# navilock-gps-to-bluetooth-converter-v1_2.net
KiCad netlist of a schematic drawn in EAGLE
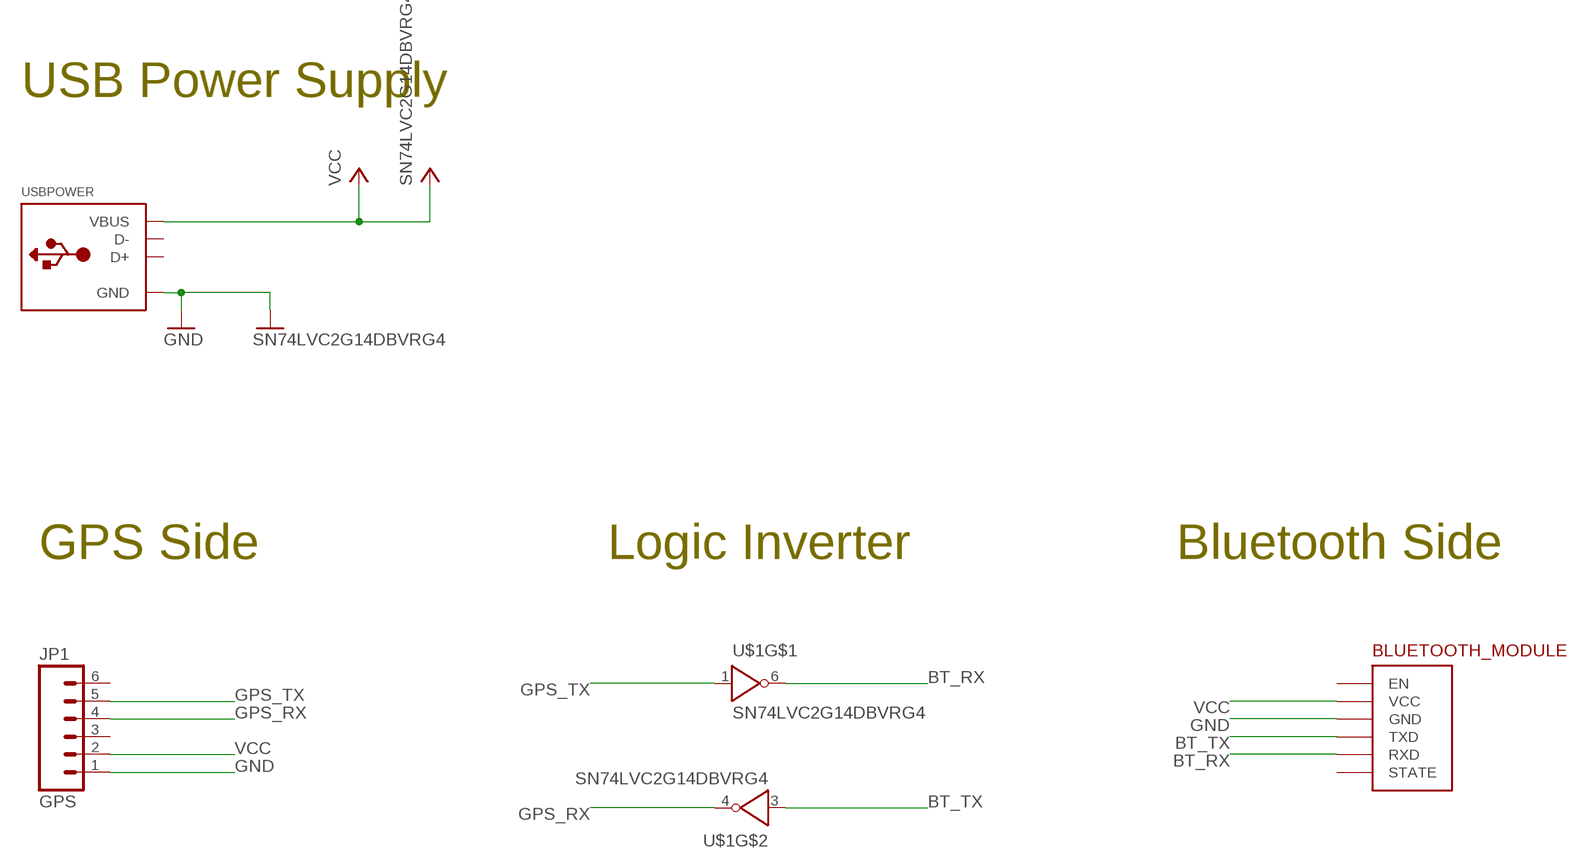
[diagram p0: schematic, sheet 1]

(export (version "E")
  (design (tool "Eeschema 10.0.6"))
  (components
    (comp (ref "BLUETOOTH_MODULE")
      (value "JY-MCU-BLUETOOTHHORIZONTAL")
      (footprint "eagle-import:JY-MCU-BLUETOOTH-HORIZONTAL")
      (libsource (lib "eagle-import") (part "JY-MCU-BLUETOOTHHORIZONTAL"))
    )
    (comp (ref "JP1")
      (value "GPS")
      (footprint "eagle-import:MINI-DIN6-WITH-LAT-HOLES")
      (libsource (lib "eagle-import") (part "MINI-DIN6WITH-LAT-HOLES"))
    )
    (comp (ref "U$1")
      (value "SN74LVC2G14DBVRG4")
      (footprint "eagle-import:SOT23-6")
      (libsource (lib "eagle-import") (part "SN74LVC2G14DBVRG4"))
    )
    (comp (ref "USBPOWER")
      (value "USB_TYPEA")
      (footprint "eagle-import:USB_A-SMT")
      (libsource (lib "eagle-import") (part "USB_TYPEA"))
    )
  )
  (nets
    (net (code "1") (name "/BT_RX") (class "Default")
      (node (ref "BLUETOOTH_MODULE") (pin "RXD") (pinfunction "RXD_RXD") (pintype "bidirectional"))
      (node (ref "U$1") (pin "6") (pinfunction "O_6") (pintype "input"))
    )
    (net (code "2") (name "/BT_TX") (class "Default")
      (node (ref "BLUETOOTH_MODULE") (pin "TXD") (pinfunction "TXD_TXD") (pintype "bidirectional"))
      (node (ref "U$1") (pin "3") (pinfunction "I_3") (pintype "input"))
    )
    (net (code "3") (name "/GPS_RX") (class "Default")
      (node (ref "JP1") (pin "4") (pinfunction "4_4") (pintype "passive"))
      (node (ref "U$1") (pin "4") (pinfunction "O_4") (pintype "input"))
    )
    (net (code "4") (name "/GPS_TX") (class "Default")
      (node (ref "JP1") (pin "5") (pinfunction "5_5") (pintype "passive"))
      (node (ref "U$1") (pin "1") (pinfunction "I_1") (pintype "input"))
    )
    (net (code "5") (name "GND") (class "Default")
      (node (ref "BLUETOOTH_MODULE") (pin "GND") (pinfunction "GND_GND") (pintype "bidirectional"))
      (node (ref "JP1") (pin "1") (pinfunction "1_1") (pintype "passive"))
      (node (ref "U$1") (pin "2") (pinfunction "GND_2") (pintype "power_in"))
      (node (ref "USBPOWER") (pin "GND") (pinfunction "GND_GND") (pintype "power_in"))
    )
    (net (code "6") (name "VCC") (class "Default")
      (node (ref "BLUETOOTH_MODULE") (pin "VCC") (pinfunction "VCC_VCC") (pintype "bidirectional"))
      (node (ref "JP1") (pin "2") (pinfunction "2_2") (pintype "passive"))
      (node (ref "U$1") (pin "5") (pinfunction "VCC_5") (pintype "power_in"))
      (node (ref "USBPOWER") (pin "VBUS") (pinfunction "VBUS_VBUS") (pintype "power_in"))
    )
    (net (code "7") (name "unconnected-(BLUETOOTH_MODULE-PadEN)") (class "Default")
      (node (ref "BLUETOOTH_MODULE") (pin "EN") (pinfunction "EN_EN") (pintype "bidirectional"))
    )
    (net (code "8") (name "unconnected-(BLUETOOTH_MODULE-PadSTATE)") (class "Default")
      (node (ref "BLUETOOTH_MODULE") (pin "STATE") (pinfunction "STATE_STATE") (pintype "bidirectional"))
    )
    (net (code "9") (name "unconnected-(JP1-Pad3)") (class "Default")
      (node (ref "JP1") (pin "3") (pinfunction "3_3") (pintype "passive"))
    )
    (net (code "10") (name "unconnected-(JP1-Pad6)") (class "Default")
      (node (ref "JP1") (pin "6") (pinfunction "6_6") (pintype "passive"))
    )
    (net (code "11") (name "unconnected-(USBPOWER-PadD+)") (class "Default")
      (node (ref "USBPOWER") (pin "D+") (pinfunction "D+_D+") (pintype "bidirectional"))
    )
    (net (code "12") (name "unconnected-(USBPOWER-PadD-)") (class "Default")
      (node (ref "USBPOWER") (pin "D-") (pinfunction "D-_D-") (pintype "bidirectional"))
    )
  )
)
